# FreeLSS_Board.net
KiCad netlist of a schematic drawn in EAGLE
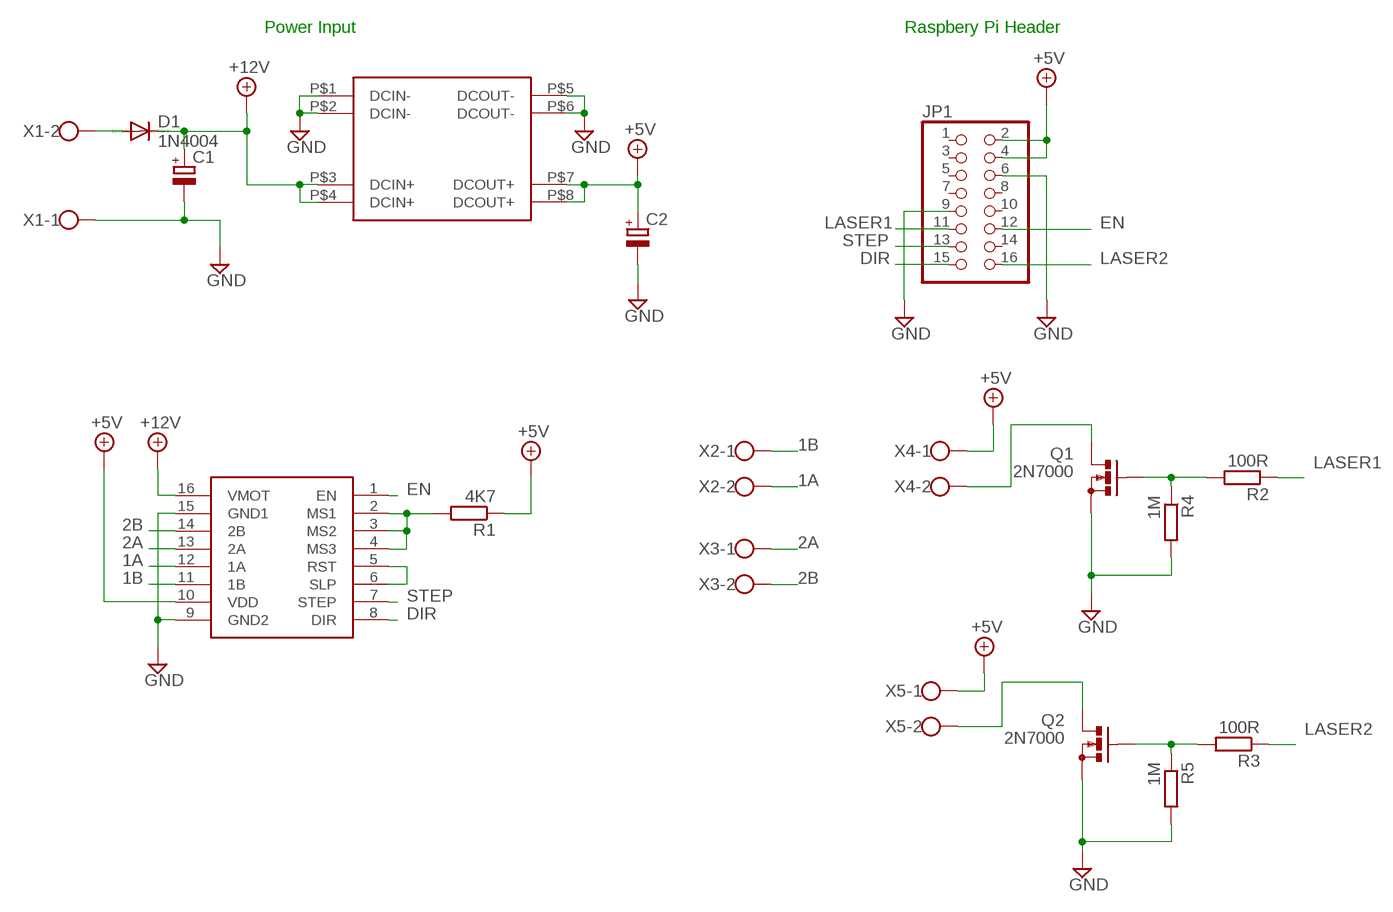
[diagram p0: schematic, sheet 1]

(export (version "E")
  (design (tool "Eeschema 10.0.6"))
  (components
    (comp (ref "C1")
      (value "CPOL-EUE2.5-5")
      (footprint "eagle-import:E2,5-5")
      (libsource (lib "eagle-import") (part "CPOL-EUE2.5-5"))
    )
    (comp (ref "C2")
      (value "CPOL-EUE2.5-5")
      (footprint "eagle-import:E2,5-5")
      (libsource (lib "eagle-import") (part "CPOL-EUE2.5-5"))
    )
    (comp (ref "D1")
      (value "1N4004")
      (footprint "eagle-import:DO35-7")
      (libsource (lib "eagle-import") (part "1N4148DO35-7"))
    )
    (comp (ref "JP1")
      (value "PINHD-2X8")
      (footprint "eagle-import:2X08")
      (libsource (lib "eagle-import") (part "PINHD-2X8"))
    )
    (comp (ref "Q1")
      (value "2N7000")
      (footprint "eagle-import:SOT54E")
      (libsource (lib "eagle-import") (part "BS170"))
    )
    (comp (ref "Q2")
      (value "2N7000")
      (footprint "eagle-import:SOT54E")
      (libsource (lib "eagle-import") (part "BS170"))
    )
    (comp (ref "R1")
      (value "4K7")
      (footprint "eagle-import:0204_7")
      (libsource (lib "eagle-import") (part "R-EU_0204/7"))
    )
    (comp (ref "R2")
      (value "100R")
      (footprint "eagle-import:0204_7")
      (libsource (lib "eagle-import") (part "R-EU_0204/7"))
    )
    (comp (ref "R3")
      (value "100R")
      (footprint "eagle-import:0204_7")
      (libsource (lib "eagle-import") (part "R-EU_0204/7"))
    )
    (comp (ref "R4")
      (value "1M")
      (footprint "eagle-import:0204_7")
      (libsource (lib "eagle-import") (part "R-EU_0204/7"))
    )
    (comp (ref "R5")
      (value "1M")
      (footprint "eagle-import:0204_7")
      (libsource (lib "eagle-import") (part "R-EU_0204/7"))
    )
    (comp (ref "U$1")
      (value "DC-DC_MODULE_MP1584")
      (footprint "eagle-import:DC-DC_MODULE_MP1584")
      (libsource (lib "eagle-import") (part "DC-DC_MODULE_MP1584"))
    )
    (comp (ref "U$2")
      (value "POLOLU_STEPSTICK")
      (footprint "eagle-import:POLOLU_STEPSTICK")
      (libsource (lib "eagle-import") (part "POLOLU_STEPSTICK"))
    )
    (comp (ref "X1")
      (value "W237-102")
      (footprint "eagle-import:W237-102")
      (fields (field (name "MPN") "237-102"))
      (libsource (lib "eagle-import") (part "W237-102"))
    )
    (comp (ref "X2")
      (value "W237-102")
      (footprint "eagle-import:W237-102")
      (fields (field (name "MPN") "237-102"))
      (libsource (lib "eagle-import") (part "W237-102"))
    )
    (comp (ref "X3")
      (value "W237-102")
      (footprint "eagle-import:W237-102")
      (fields (field (name "MPN") "237-102"))
      (libsource (lib "eagle-import") (part "W237-102"))
    )
    (comp (ref "X4")
      (value "W237-102")
      (footprint "eagle-import:W237-102")
      (fields (field (name "MPN") "237-102"))
      (libsource (lib "eagle-import") (part "W237-102"))
    )
    (comp (ref "X5")
      (value "W237-102")
      (footprint "eagle-import:W237-102")
      (fields (field (name "MPN") "237-102"))
      (libsource (lib "eagle-import") (part "W237-102"))
    )
  )
  (nets
    (net (code "1") (name "+5V") (class "Default")
      (node (ref "C2") (pin "+") (pinfunction "+_+") (pintype "passive"))
      (node (ref "JP1") (pin "2") (pinfunction "2_2") (pintype "passive"))
      (node (ref "JP1") (pin "4") (pinfunction "4_4") (pintype "passive"))
      (node (ref "R1") (pin "1") (pinfunction "1_1") (pintype "passive"))
      (node (ref "U$1") (pin "P$7") (pinfunction "DCOUT+_P$7") (pintype "output"))
      (node (ref "U$1") (pin "P$8") (pinfunction "DCOUT+_P$8") (pintype "output"))
      (node (ref "U$2") (pin "10") (pinfunction "VDD_10") (pintype "power_in"))
      (node (ref "X4") (pin "1") (pinfunction "KL_1") (pintype "passive"))
      (node (ref "X5") (pin "1") (pinfunction "KL_1") (pintype "passive"))
    )
    (net (code "2") (name "+12V") (class "Default")
      (node (ref "C1") (pin "+") (pinfunction "+_+") (pintype "passive"))
      (node (ref "D1") (pin "C") (pinfunction "C_C") (pintype "passive"))
      (node (ref "U$1") (pin "P$3") (pinfunction "DCIN+_P$3") (pintype "input"))
      (node (ref "U$1") (pin "P$4") (pinfunction "DCIN+_P$4") (pintype "input"))
      (node (ref "U$2") (pin "16") (pinfunction "VMOT_16") (pintype "power_in"))
    )
    (net (code "3") (name "/1A") (class "Default")
      (node (ref "U$2") (pin "12") (pinfunction "1A_12") (pintype "output"))
      (node (ref "X2") (pin "2") (pinfunction "KL_2") (pintype "passive"))
    )
    (net (code "4") (name "/1B") (class "Default")
      (node (ref "U$2") (pin "11") (pinfunction "1B_11") (pintype "output"))
      (node (ref "X2") (pin "1") (pinfunction "KL_1") (pintype "passive"))
    )
    (net (code "5") (name "/2A") (class "Default")
      (node (ref "U$2") (pin "13") (pinfunction "2A_13") (pintype "output"))
      (node (ref "X3") (pin "1") (pinfunction "KL_1") (pintype "passive"))
    )
    (net (code "6") (name "/2B") (class "Default")
      (node (ref "U$2") (pin "14") (pinfunction "2B_14") (pintype "output"))
      (node (ref "X3") (pin "2") (pinfunction "KL_2") (pintype "passive"))
    )
    (net (code "7") (name "/DIR") (class "Default")
      (node (ref "JP1") (pin "15") (pinfunction "15_15") (pintype "passive"))
      (node (ref "U$2") (pin "8") (pinfunction "DIR_8") (pintype "input"))
    )
    (net (code "8") (name "/EN") (class "Default")
      (node (ref "JP1") (pin "12") (pinfunction "12_12") (pintype "passive"))
      (node (ref "U$2") (pin "1") (pinfunction "EN_1") (pintype "input"))
    )
    (net (code "9") (name "/LASER1") (class "Default")
      (node (ref "JP1") (pin "11") (pinfunction "11_11") (pintype "passive"))
      (node (ref "R2") (pin "1") (pinfunction "1_1") (pintype "passive"))
    )
    (net (code "10") (name "/LASER2") (class "Default")
      (node (ref "JP1") (pin "16") (pinfunction "16_16") (pintype "passive"))
      (node (ref "R3") (pin "1") (pinfunction "1_1") (pintype "passive"))
    )
    (net (code "11") (name "/STEP") (class "Default")
      (node (ref "JP1") (pin "13") (pinfunction "13_13") (pintype "passive"))
      (node (ref "U$2") (pin "7") (pinfunction "STEP_7") (pintype "input"))
    )
    (net (code "12") (name "GND") (class "Default")
      (node (ref "C1") (pin "-") (pinfunction "-_-") (pintype "passive"))
      (node (ref "C2") (pin "-") (pinfunction "-_-") (pintype "passive"))
      (node (ref "JP1") (pin "6") (pinfunction "6_6") (pintype "passive"))
      (node (ref "JP1") (pin "9") (pinfunction "9_9") (pintype "passive"))
      (node (ref "Q1") (pin "S") (pinfunction "S_S") (pintype "passive"))
      (node (ref "Q2") (pin "S") (pinfunction "S_S") (pintype "passive"))
      (node (ref "R4") (pin "2") (pinfunction "2_2") (pintype "passive"))
      (node (ref "R5") (pin "2") (pinfunction "2_2") (pintype "passive"))
      (node (ref "U$1") (pin "P$1") (pinfunction "DCIN-_P$1") (pintype "input"))
      (node (ref "U$1") (pin "P$2") (pinfunction "DCIN-_P$2") (pintype "input"))
      (node (ref "U$1") (pin "P$5") (pinfunction "DCOUT-_P$5") (pintype "output"))
      (node (ref "U$1") (pin "P$6") (pinfunction "DCOUT-_P$6") (pintype "output"))
      (node (ref "U$2") (pin "15") (pinfunction "GND1_15") (pintype "power_in"))
      (node (ref "U$2") (pin "9") (pinfunction "GND2_9") (pintype "power_in"))
      (node (ref "X1") (pin "1") (pinfunction "KL_1") (pintype "passive"))
    )
    (net (code "13") (name "Net-(Q1-PadG)") (class "Default")
      (node (ref "Q1") (pin "G") (pinfunction "G_G") (pintype "passive"))
      (node (ref "R2") (pin "2") (pinfunction "2_2") (pintype "passive"))
      (node (ref "R4") (pin "1") (pinfunction "1_1") (pintype "passive"))
    )
    (net (code "14") (name "Net-(Q2-PadG)") (class "Default")
      (node (ref "Q2") (pin "G") (pinfunction "G_G") (pintype "passive"))
      (node (ref "R3") (pin "2") (pinfunction "2_2") (pintype "passive"))
      (node (ref "R5") (pin "1") (pinfunction "1_1") (pintype "passive"))
    )
    (net (code "15") (name "Net-(U$2-MS1)") (class "Default")
      (node (ref "R1") (pin "2") (pinfunction "2_2") (pintype "passive"))
      (node (ref "U$2") (pin "2") (pinfunction "MS1_2") (pintype "input"))
      (node (ref "U$2") (pin "3") (pinfunction "MS2_3") (pintype "input"))
      (node (ref "U$2") (pin "4") (pinfunction "MS3_4") (pintype "input"))
    )
    (net (code "16") (name "Net-(U$2-RST)") (class "Default")
      (node (ref "U$2") (pin "5") (pinfunction "RST_5") (pintype "input"))
      (node (ref "U$2") (pin "6") (pinfunction "SLP_6") (pintype "input"))
    )
    (net (code "17") (name "Net-(X1B-KL)") (class "Default")
      (node (ref "D1") (pin "A") (pinfunction "A_A") (pintype "passive"))
      (node (ref "X1") (pin "2") (pinfunction "KL_2") (pintype "passive"))
    )
    (net (code "18") (name "Net-(X4B-KL)") (class "Default")
      (node (ref "Q1") (pin "D") (pinfunction "D_D") (pintype "passive"))
      (node (ref "X4") (pin "2") (pinfunction "KL_2") (pintype "passive"))
    )
    (net (code "19") (name "Net-(X5B-KL)") (class "Default")
      (node (ref "Q2") (pin "D") (pinfunction "D_D") (pintype "passive"))
      (node (ref "X5") (pin "2") (pinfunction "KL_2") (pintype "passive"))
    )
    (net (code "20") (name "unconnected-(JP1-Pad1)") (class "Default")
      (node (ref "JP1") (pin "1") (pinfunction "1_1") (pintype "passive"))
    )
    (net (code "21") (name "unconnected-(JP1-Pad3)") (class "Default")
      (node (ref "JP1") (pin "3") (pinfunction "3_3") (pintype "passive"))
    )
    (net (code "22") (name "unconnected-(JP1-Pad5)") (class "Default")
      (node (ref "JP1") (pin "5") (pinfunction "5_5") (pintype "passive"))
    )
    (net (code "23") (name "unconnected-(JP1-Pad7)") (class "Default")
      (node (ref "JP1") (pin "7") (pinfunction "7_7") (pintype "passive"))
    )
    (net (code "24") (name "unconnected-(JP1-Pad8)") (class "Default")
      (node (ref "JP1") (pin "8") (pinfunction "8_8") (pintype "passive"))
    )
    (net (code "25") (name "unconnected-(JP1-Pad10)") (class "Default")
      (node (ref "JP1") (pin "10") (pinfunction "10_10") (pintype "passive"))
    )
    (net (code "26") (name "unconnected-(JP1-Pad14)") (class "Default")
      (node (ref "JP1") (pin "14") (pinfunction "14_14") (pintype "passive"))
    )
  )
)
